# Daughter_Board_2_1.net
KiCad netlist of a schematic drawn in EAGLE
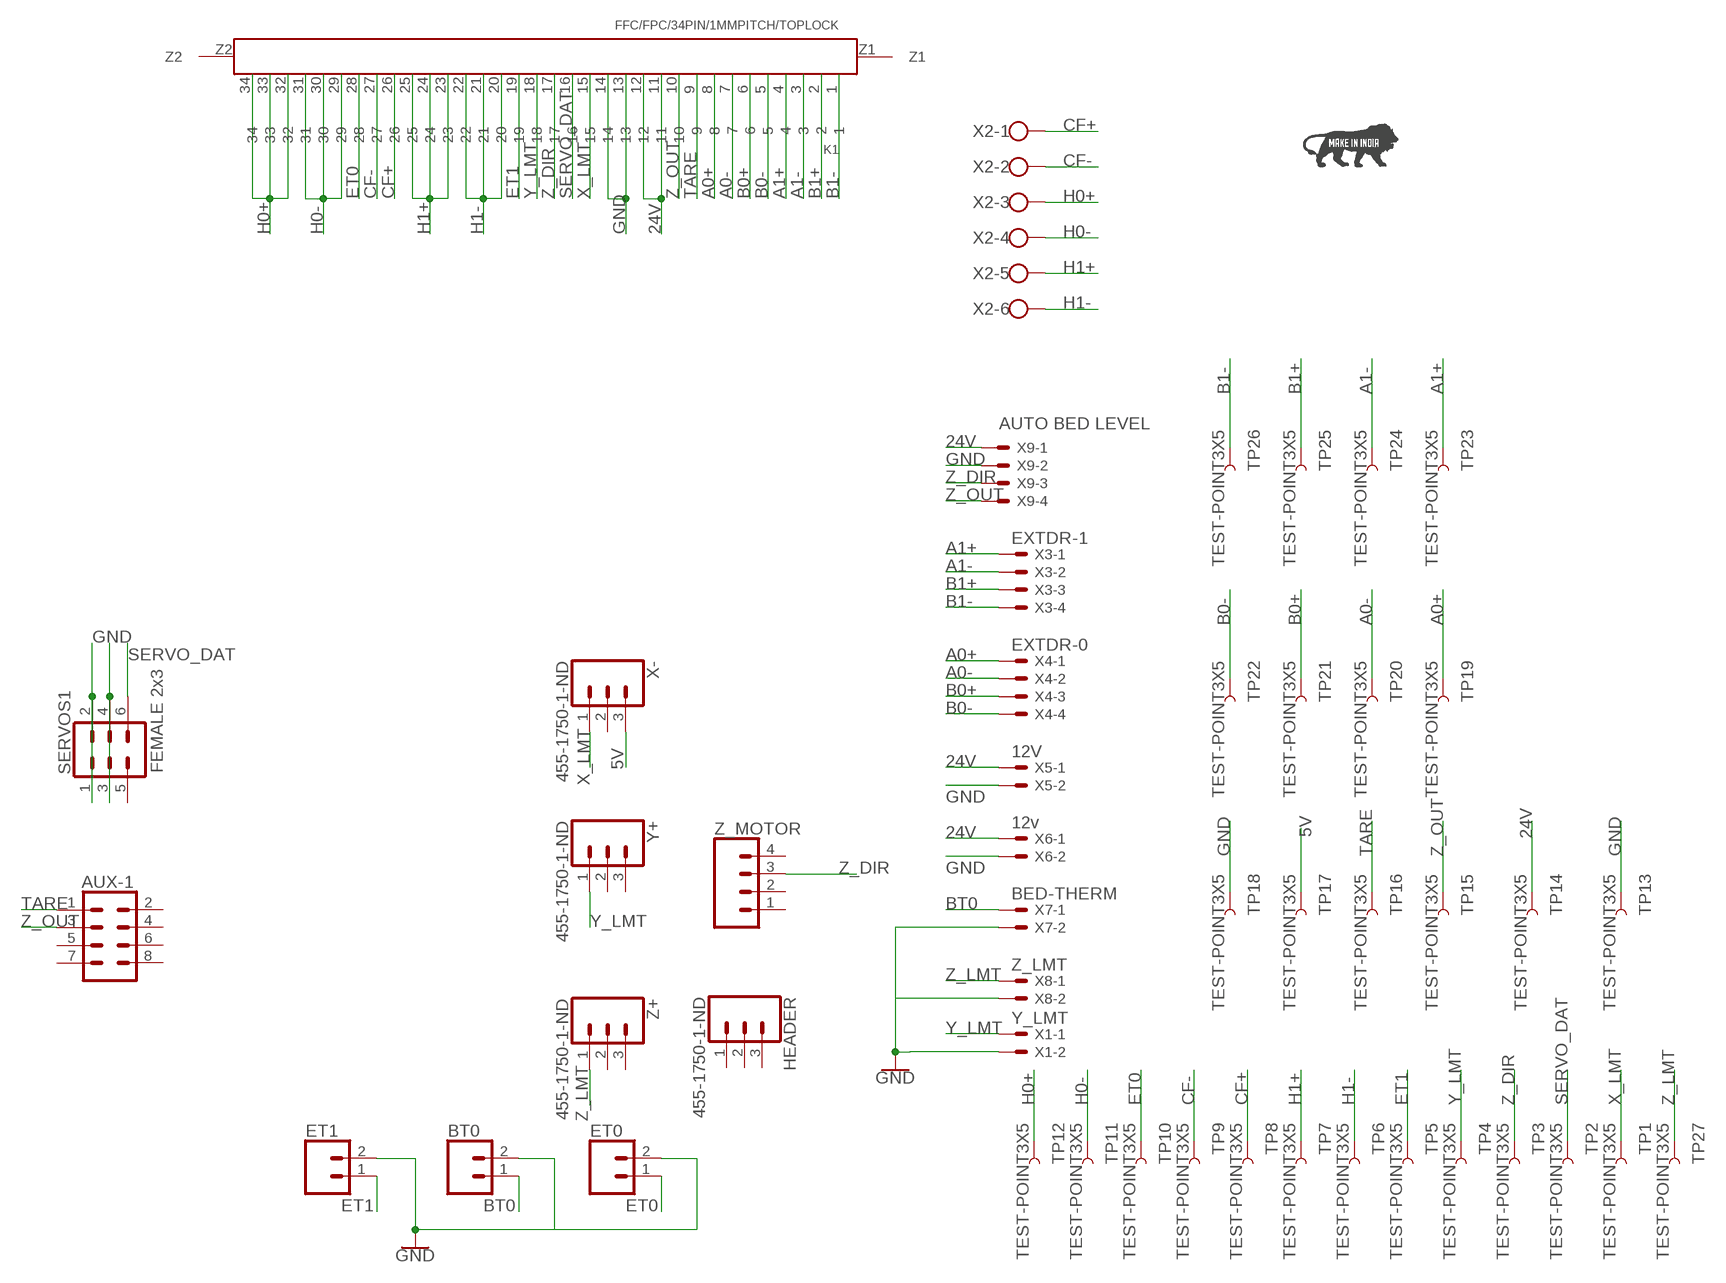
[diagram p0: schematic, sheet 1]

(export (version "E")
  (design (tool "Eeschema 10.0.6"))
  (components
    (comp (ref "AUX-1")
      (value "CONN_04X2")
      (footprint "eagle-import:2X4")
      (libsource (lib "eagle-import") (part "CONN_04X2"))
    )
    (comp (ref "BT0")
      (value "CONN_02")
      (footprint "eagle-import:1X02")
      (libsource (lib "eagle-import") (part "CONN_02"))
    )
    (comp (ref "ET0")
      (value "CONN_02")
      (footprint "eagle-import:1X02")
      (libsource (lib "eagle-import") (part "CONN_02"))
    )
    (comp (ref "ET1")
      (value "CONN_02")
      (footprint "eagle-import:1X02")
      (libsource (lib "eagle-import") (part "CONN_02"))
    )
    (comp (ref "HEADER")
      (value "455-1750-1-ND")
      (footprint "eagle-import:1X03")
      (libsource (lib "eagle-import") (part "CONN_03"))
    )
    (comp (ref "K1")
      (value "FFC/FPC/34PIN/1MMPITCH/TOPLOCK")
      (footprint "eagle-import:34PIN_1MMPITCH_FFC_FPC")
      (libsource (lib "eagle-import") (part "FFC/FPC/34PIN/1MMPITCH/TOPLOCK"))
    )
    (comp (ref "SERVOS1")
      (value "FEMALE 2x3")
      (footprint "eagle-import:2X3")
      (libsource (lib "eagle-import") (part "CONN_03X2FEMALE"))
    )
    (comp (ref "TP1")
      (value "TEST-POINT3X5")
      (footprint "eagle-import:PAD.03X.05")
      (libsource (lib "eagle-import") (part "TEST-POINT3X5"))
    )
    (comp (ref "TP2")
      (value "TEST-POINT3X5")
      (footprint "eagle-import:PAD.03X.05")
      (libsource (lib "eagle-import") (part "TEST-POINT3X5"))
    )
    (comp (ref "TP3")
      (value "TEST-POINT3X5")
      (footprint "eagle-import:PAD.03X.05")
      (libsource (lib "eagle-import") (part "TEST-POINT3X5"))
    )
    (comp (ref "TP4")
      (value "TEST-POINT3X5")
      (footprint "eagle-import:PAD.03X.05")
      (libsource (lib "eagle-import") (part "TEST-POINT3X5"))
    )
    (comp (ref "TP5")
      (value "TEST-POINT3X5")
      (footprint "eagle-import:PAD.03X.05")
      (libsource (lib "eagle-import") (part "TEST-POINT3X5"))
    )
    (comp (ref "TP6")
      (value "TEST-POINT3X5")
      (footprint "eagle-import:PAD.03X.05")
      (libsource (lib "eagle-import") (part "TEST-POINT3X5"))
    )
    (comp (ref "TP7")
      (value "TEST-POINT3X5")
      (footprint "eagle-import:PAD.03X.05")
      (libsource (lib "eagle-import") (part "TEST-POINT3X5"))
    )
    (comp (ref "TP8")
      (value "TEST-POINT3X5")
      (footprint "eagle-import:PAD.03X.05")
      (libsource (lib "eagle-import") (part "TEST-POINT3X5"))
    )
    (comp (ref "TP9")
      (value "TEST-POINT3X5")
      (footprint "eagle-import:PAD.03X.05")
      (libsource (lib "eagle-import") (part "TEST-POINT3X5"))
    )
    (comp (ref "TP10")
      (value "TEST-POINT3X5")
      (footprint "eagle-import:PAD.03X.05")
      (libsource (lib "eagle-import") (part "TEST-POINT3X5"))
    )
    (comp (ref "TP11")
      (value "TEST-POINT3X5")
      (footprint "eagle-import:PAD.03X.05")
      (libsource (lib "eagle-import") (part "TEST-POINT3X5"))
    )
    (comp (ref "TP12")
      (value "TEST-POINT3X5")
      (footprint "eagle-import:PAD.03X.05")
      (libsource (lib "eagle-import") (part "TEST-POINT3X5"))
    )
    (comp (ref "TP13")
      (value "TEST-POINT3X5")
      (footprint "eagle-import:PAD.03X.05")
      (libsource (lib "eagle-import") (part "TEST-POINT3X5"))
    )
    (comp (ref "TP14")
      (value "TEST-POINT3X5")
      (footprint "eagle-import:PAD.03X.05")
      (libsource (lib "eagle-import") (part "TEST-POINT3X5"))
    )
    (comp (ref "TP15")
      (value "TEST-POINT3X5")
      (footprint "eagle-import:PAD.03X.05")
      (libsource (lib "eagle-import") (part "TEST-POINT3X5"))
    )
    (comp (ref "TP16")
      (value "TEST-POINT3X5")
      (footprint "eagle-import:PAD.03X.05")
      (libsource (lib "eagle-import") (part "TEST-POINT3X5"))
    )
    (comp (ref "TP17")
      (value "TEST-POINT3X5")
      (footprint "eagle-import:PAD.03X.05")
      (libsource (lib "eagle-import") (part "TEST-POINT3X5"))
    )
    (comp (ref "TP18")
      (value "TEST-POINT3X5")
      (footprint "eagle-import:PAD.03X.05")
      (libsource (lib "eagle-import") (part "TEST-POINT3X5"))
    )
    (comp (ref "TP19")
      (value "TEST-POINT3X5")
      (footprint "eagle-import:PAD.03X.05")
      (libsource (lib "eagle-import") (part "TEST-POINT3X5"))
    )
    (comp (ref "TP20")
      (value "TEST-POINT3X5")
      (footprint "eagle-import:PAD.03X.05")
      (libsource (lib "eagle-import") (part "TEST-POINT3X5"))
    )
    (comp (ref "TP21")
      (value "TEST-POINT3X5")
      (footprint "eagle-import:PAD.03X.05")
      (libsource (lib "eagle-import") (part "TEST-POINT3X5"))
    )
    (comp (ref "TP22")
      (value "TEST-POINT3X5")
      (footprint "eagle-import:PAD.03X.05")
      (libsource (lib "eagle-import") (part "TEST-POINT3X5"))
    )
    (comp (ref "TP23")
      (value "TEST-POINT3X5")
      (footprint "eagle-import:PAD.03X.05")
      (libsource (lib "eagle-import") (part "TEST-POINT3X5"))
    )
    (comp (ref "TP24")
      (value "TEST-POINT3X5")
      (footprint "eagle-import:PAD.03X.05")
      (libsource (lib "eagle-import") (part "TEST-POINT3X5"))
    )
    (comp (ref "TP25")
      (value "TEST-POINT3X5")
      (footprint "eagle-import:PAD.03X.05")
      (libsource (lib "eagle-import") (part "TEST-POINT3X5"))
    )
    (comp (ref "TP26")
      (value "TEST-POINT3X5")
      (footprint "eagle-import:PAD.03X.05")
      (libsource (lib "eagle-import") (part "TEST-POINT3X5"))
    )
    (comp (ref "TP27")
      (value "TEST-POINT3X5")
      (footprint "eagle-import:PAD.03X.05")
      (libsource (lib "eagle-import") (part "TEST-POINT3X5"))
    )
    (comp (ref "U$2")
      (value "MAKEININDIA")
      (footprint "eagle-import:MAKEININDIA")
      (libsource (lib "eagle-import") (part "MAKEININDIA"))
    )
    (comp (ref "X-")
      (value "455-1750-1-ND")
      (footprint "eagle-import:1X03")
      (libsource (lib "eagle-import") (part "CONN_03"))
    )
    (comp (ref "X1")
      (value "Y_LMT")
      (footprint "eagle-import:JST-XH-02-PACKAGE-LONG-PAD")
      (libsource (lib "eagle-import") (part "JST-XH-02-PIN-LONG-PAD"))
    )
    (comp (ref "X2")
      (value "W237-6")
      (footprint "eagle-import:W237-6")
      (libsource (lib "eagle-import") (part "W237-6"))
    )
    (comp (ref "X3")
      (value "EXTDR-1")
      (footprint "eagle-import:JST-XH-04-PACKAGE-LONG-PAD")
      (libsource (lib "eagle-import") (part "JST-XH-04-PIN-LONG-PAD"))
    )
    (comp (ref "X4")
      (value "EXTDR-0")
      (footprint "eagle-import:JST-XH-04-PACKAGE-LONG-PAD")
      (libsource (lib "eagle-import") (part "JST-XH-04-PIN-LONG-PAD"))
    )
    (comp (ref "X5")
      (value "12V")
      (footprint "eagle-import:JST-XH-02-PACKAGE-LONG-PAD")
      (libsource (lib "eagle-import") (part "JST-XH-02-PIN-LONG-PAD"))
    )
    (comp (ref "X6")
      (value "12v")
      (footprint "eagle-import:JST-XH-02-PACKAGE-LONG-PAD")
      (libsource (lib "eagle-import") (part "JST-XH-02-PIN-LONG-PAD"))
    )
    (comp (ref "X7")
      (value "BED-THERM")
      (footprint "eagle-import:JST-XH-02-PACKAGE-LONG-PAD")
      (libsource (lib "eagle-import") (part "JST-XH-02-PIN-LONG-PAD"))
    )
    (comp (ref "X8")
      (value "Z_LMT")
      (footprint "eagle-import:JST-XH-02-PACKAGE-LONG-PAD")
      (libsource (lib "eagle-import") (part "JST-XH-02-PIN-LONG-PAD"))
    )
    (comp (ref "X9")
      (value "JST-XH-04-PIN-LONG-PAD")
      (footprint "eagle-import:JST-XH-04-PACKAGE-LONG-PAD")
      (fields (field (name "AUTOBEDLEVL") "AUTO BED LEVEL"))
      (libsource (lib "eagle-import") (part "JST-XH-04-PIN-LONG-PAD"))
    )
    (comp (ref "Y+")
      (value "455-1750-1-ND")
      (footprint "eagle-import:1X03")
      (libsource (lib "eagle-import") (part "CONN_03"))
    )
    (comp (ref "Z+")
      (value "455-1750-1-ND")
      (footprint "eagle-import:1X03")
      (libsource (lib "eagle-import") (part "CONN_03"))
    )
    (comp (ref "Z_MOTOR")
      (value "CONN_04")
      (footprint "eagle-import:1X04")
      (libsource (lib "eagle-import") (part "CONN_04"))
    )
  )
  (nets
    (net (code "1") (name "/5V") (class "Default")
      (node (ref "TP17") (pin "P$1") (pinfunction "1_P$1") (pintype "bidirectional"))
      (node (ref "X-") (pin "3") (pinfunction "3_3") (pintype "passive"))
    )
    (net (code "2") (name "/24V") (class "Default")
      (node (ref "K1") (pin "11") (pinfunction "11_11") (pintype "bidirectional"))
      (node (ref "K1") (pin "12") (pinfunction "12_12") (pintype "bidirectional"))
      (node (ref "TP14") (pin "P$1") (pinfunction "1_P$1") (pintype "bidirectional"))
      (node (ref "X5") (pin "1") (pinfunction "S_1") (pintype "passive"))
      (node (ref "X6") (pin "1") (pinfunction "S_1") (pintype "passive"))
      (node (ref "X9") (pin "1") (pinfunction "S_1") (pintype "passive"))
    )
    (net (code "3") (name "/A0+") (class "Default")
      (node (ref "K1") (pin "8") (pinfunction "8_8") (pintype "bidirectional"))
      (node (ref "TP19") (pin "P$1") (pinfunction "1_P$1") (pintype "bidirectional"))
      (node (ref "X4") (pin "1") (pinfunction "S_1") (pintype "passive"))
    )
    (net (code "4") (name "/A0-") (class "Default")
      (node (ref "K1") (pin "7") (pinfunction "7_7") (pintype "bidirectional"))
      (node (ref "TP20") (pin "P$1") (pinfunction "1_P$1") (pintype "bidirectional"))
      (node (ref "X4") (pin "2") (pinfunction "S_2") (pintype "passive"))
    )
    (net (code "5") (name "/A1+") (class "Default")
      (node (ref "K1") (pin "4") (pinfunction "4_4") (pintype "bidirectional"))
      (node (ref "TP23") (pin "P$1") (pinfunction "1_P$1") (pintype "bidirectional"))
      (node (ref "X3") (pin "1") (pinfunction "S_1") (pintype "passive"))
    )
    (net (code "6") (name "/A1-") (class "Default")
      (node (ref "K1") (pin "3") (pinfunction "3_3") (pintype "bidirectional"))
      (node (ref "TP24") (pin "P$1") (pinfunction "1_P$1") (pintype "bidirectional"))
      (node (ref "X3") (pin "2") (pinfunction "S_2") (pintype "passive"))
    )
    (net (code "7") (name "/B0+") (class "Default")
      (node (ref "K1") (pin "6") (pinfunction "6_6") (pintype "bidirectional"))
      (node (ref "TP21") (pin "P$1") (pinfunction "1_P$1") (pintype "bidirectional"))
      (node (ref "X4") (pin "3") (pinfunction "S_3") (pintype "passive"))
    )
    (net (code "8") (name "/B0-") (class "Default")
      (node (ref "K1") (pin "5") (pinfunction "5_5") (pintype "bidirectional"))
      (node (ref "TP22") (pin "P$1") (pinfunction "1_P$1") (pintype "bidirectional"))
      (node (ref "X4") (pin "4") (pinfunction "S_4") (pintype "passive"))
    )
    (net (code "9") (name "/B1+") (class "Default")
      (node (ref "K1") (pin "2") (pinfunction "2_2") (pintype "bidirectional"))
      (node (ref "TP25") (pin "P$1") (pinfunction "1_P$1") (pintype "bidirectional"))
      (node (ref "X3") (pin "3") (pinfunction "S_3") (pintype "passive"))
    )
    (net (code "10") (name "/B1-") (class "Default")
      (node (ref "K1") (pin "1") (pinfunction "1_1") (pintype "bidirectional"))
      (node (ref "TP26") (pin "P$1") (pinfunction "1_P$1") (pintype "bidirectional"))
      (node (ref "X3") (pin "4") (pinfunction "S_4") (pintype "passive"))
    )
    (net (code "11") (name "/BT0") (class "Default")
      (node (ref "BT0") (pin "1") (pinfunction "1_1") (pintype "passive"))
      (node (ref "X7") (pin "1") (pinfunction "S_1") (pintype "passive"))
    )
    (net (code "12") (name "/CF+") (class "Default")
      (node (ref "K1") (pin "26") (pinfunction "26_26") (pintype "bidirectional"))
      (node (ref "TP8") (pin "P$1") (pinfunction "1_P$1") (pintype "bidirectional"))
      (node (ref "X2") (pin "1") (pinfunction "KL_1") (pintype "passive"))
    )
    (net (code "13") (name "/CF-") (class "Default")
      (node (ref "K1") (pin "27") (pinfunction "27_27") (pintype "bidirectional"))
      (node (ref "TP9") (pin "P$1") (pinfunction "1_P$1") (pintype "bidirectional"))
      (node (ref "X2") (pin "2") (pinfunction "KL_2") (pintype "passive"))
    )
    (net (code "14") (name "/ET0") (class "Default")
      (node (ref "ET0") (pin "1") (pinfunction "1_1") (pintype "passive"))
      (node (ref "K1") (pin "28") (pinfunction "28_28") (pintype "bidirectional"))
      (node (ref "TP10") (pin "P$1") (pinfunction "1_P$1") (pintype "bidirectional"))
    )
    (net (code "15") (name "/ET1") (class "Default")
      (node (ref "ET1") (pin "1") (pinfunction "1_1") (pintype "passive"))
      (node (ref "K1") (pin "19") (pinfunction "19_19") (pintype "bidirectional"))
      (node (ref "TP5") (pin "P$1") (pinfunction "1_P$1") (pintype "bidirectional"))
    )
    (net (code "16") (name "/H0+") (class "Default")
      (node (ref "K1") (pin "32") (pinfunction "32_32") (pintype "bidirectional"))
      (node (ref "K1") (pin "33") (pinfunction "33_33") (pintype "bidirectional"))
      (node (ref "K1") (pin "34") (pinfunction "34_34") (pintype "bidirectional"))
      (node (ref "TP12") (pin "P$1") (pinfunction "1_P$1") (pintype "bidirectional"))
      (node (ref "X2") (pin "3") (pinfunction "KL_3") (pintype "passive"))
    )
    (net (code "17") (name "/H0-") (class "Default")
      (node (ref "K1") (pin "29") (pinfunction "29_29") (pintype "bidirectional"))
      (node (ref "K1") (pin "30") (pinfunction "30_30") (pintype "bidirectional"))
      (node (ref "K1") (pin "31") (pinfunction "31_31") (pintype "bidirectional"))
      (node (ref "TP11") (pin "P$1") (pinfunction "1_P$1") (pintype "bidirectional"))
      (node (ref "X2") (pin "4") (pinfunction "KL_4") (pintype "passive"))
    )
    (net (code "18") (name "/H1+") (class "Default")
      (node (ref "K1") (pin "23") (pinfunction "23_23") (pintype "bidirectional"))
      (node (ref "K1") (pin "24") (pinfunction "24_24") (pintype "bidirectional"))
      (node (ref "K1") (pin "25") (pinfunction "25_25") (pintype "bidirectional"))
      (node (ref "TP7") (pin "P$1") (pinfunction "1_P$1") (pintype "bidirectional"))
      (node (ref "X2") (pin "5") (pinfunction "KL_5") (pintype "passive"))
    )
    (net (code "19") (name "/H1-") (class "Default")
      (node (ref "K1") (pin "20") (pinfunction "20_20") (pintype "bidirectional"))
      (node (ref "K1") (pin "21") (pinfunction "21_21") (pintype "bidirectional"))
      (node (ref "K1") (pin "22") (pinfunction "22_22") (pintype "bidirectional"))
      (node (ref "TP6") (pin "P$1") (pinfunction "1_P$1") (pintype "bidirectional"))
      (node (ref "X2") (pin "6") (pinfunction "KL_6") (pintype "passive"))
    )
    (net (code "20") (name "/SERVO_DAT") (class "Default")
      (node (ref "K1") (pin "16") (pinfunction "16_16") (pintype "bidirectional"))
      (node (ref "SERVOS1") (pin "6") (pinfunction "6_6") (pintype "bidirectional"))
      (node (ref "TP2") (pin "P$1") (pinfunction "1_P$1") (pintype "bidirectional"))
    )
    (net (code "21") (name "/TARE") (class "Default")
      (node (ref "AUX-1") (pin "1") (pinfunction "1_1") (pintype "passive"))
      (node (ref "K1") (pin "9") (pinfunction "9_9") (pintype "bidirectional"))
      (node (ref "TP16") (pin "P$1") (pinfunction "1_P$1") (pintype "bidirectional"))
    )
    (net (code "22") (name "/X_LMT") (class "Default")
      (node (ref "K1") (pin "15") (pinfunction "15_15") (pintype "bidirectional"))
      (node (ref "TP1") (pin "P$1") (pinfunction "1_P$1") (pintype "bidirectional"))
      (node (ref "X-") (pin "1") (pinfunction "1_1") (pintype "passive"))
    )
    (net (code "23") (name "/Y_LMT") (class "Default")
      (node (ref "K1") (pin "18") (pinfunction "18_18") (pintype "bidirectional"))
      (node (ref "TP4") (pin "P$1") (pinfunction "1_P$1") (pintype "bidirectional"))
      (node (ref "X1") (pin "1") (pinfunction "S_1") (pintype "passive"))
      (node (ref "Y+") (pin "1") (pinfunction "1_1") (pintype "passive"))
    )
    (net (code "24") (name "/Z_DIR") (class "Default")
      (node (ref "K1") (pin "17") (pinfunction "17_17") (pintype "bidirectional"))
      (node (ref "TP3") (pin "P$1") (pinfunction "1_P$1") (pintype "bidirectional"))
      (node (ref "X9") (pin "3") (pinfunction "S_3") (pintype "passive"))
      (node (ref "Z_MOTOR") (pin "3") (pinfunction "3_3") (pintype "passive"))
    )
    (net (code "25") (name "/Z_LMT") (class "Default")
      (node (ref "TP27") (pin "P$1") (pinfunction "1_P$1") (pintype "bidirectional"))
      (node (ref "X8") (pin "1") (pinfunction "S_1") (pintype "passive"))
      (node (ref "Z+") (pin "1") (pinfunction "1_1") (pintype "passive"))
    )
    (net (code "26") (name "/Z_OUT") (class "Default")
      (node (ref "AUX-1") (pin "3") (pinfunction "3_3") (pintype "passive"))
      (node (ref "K1") (pin "10") (pinfunction "10_10") (pintype "bidirectional"))
      (node (ref "TP15") (pin "P$1") (pinfunction "1_P$1") (pintype "bidirectional"))
      (node (ref "X9") (pin "4") (pinfunction "S_4") (pintype "passive"))
    )
    (net (code "27") (name "GND") (class "Default")
      (node (ref "BT0") (pin "2") (pinfunction "2_2") (pintype "passive"))
      (node (ref "ET0") (pin "2") (pinfunction "2_2") (pintype "passive"))
      (node (ref "ET1") (pin "2") (pinfunction "2_2") (pintype "passive"))
      (node (ref "K1") (pin "13") (pinfunction "13_13") (pintype "bidirectional"))
      (node (ref "K1") (pin "14") (pinfunction "14_14") (pintype "bidirectional"))
      (node (ref "SERVOS1") (pin "1") (pinfunction "1_1") (pintype "bidirectional"))
      (node (ref "SERVOS1") (pin "2") (pinfunction "2_2") (pintype "bidirectional"))
      (node (ref "TP13") (pin "P$1") (pinfunction "1_P$1") (pintype "bidirectional"))
      (node (ref "TP18") (pin "P$1") (pinfunction "1_P$1") (pintype "bidirectional"))
      (node (ref "X1") (pin "2") (pinfunction "S_2") (pintype "passive"))
      (node (ref "X5") (pin "2") (pinfunction "S_2") (pintype "passive"))
      (node (ref "X6") (pin "2") (pinfunction "S_2") (pintype "passive"))
      (node (ref "X7") (pin "2") (pinfunction "S_2") (pintype "passive"))
      (node (ref "X8") (pin "2") (pinfunction "S_2") (pintype "passive"))
      (node (ref "X9") (pin "2") (pinfunction "S_2") (pintype "passive"))
    )
    (net (code "28") (name "Net-(SERVOS1-Pad3)") (class "Default")
      (node (ref "SERVOS1") (pin "3") (pinfunction "3_3") (pintype "bidirectional"))
      (node (ref "SERVOS1") (pin "4") (pinfunction "4_4") (pintype "bidirectional"))
    )
    (net (code "29") (name "unconnected-(AUX-1-Pad2)") (class "Default")
      (node (ref "AUX-1") (pin "2") (pinfunction "2_2") (pintype "passive"))
    )
    (net (code "30") (name "unconnected-(AUX-1-Pad4)") (class "Default")
      (node (ref "AUX-1") (pin "4") (pinfunction "4_4") (pintype "passive"))
    )
    (net (code "31") (name "unconnected-(AUX-1-Pad5)") (class "Default")
      (node (ref "AUX-1") (pin "5") (pinfunction "5_5") (pintype "passive"))
    )
    (net (code "32") (name "unconnected-(AUX-1-Pad6)") (class "Default")
      (node (ref "AUX-1") (pin "6") (pinfunction "6_6") (pintype "passive"))
    )
    (net (code "33") (name "unconnected-(AUX-1-Pad7)") (class "Default")
      (node (ref "AUX-1") (pin "7") (pinfunction "7_7") (pintype "passive"))
    )
    (net (code "34") (name "unconnected-(AUX-1-Pad8)") (class "Default")
      (node (ref "AUX-1") (pin "8") (pinfunction "8_8") (pintype "passive"))
    )
    (net (code "35") (name "unconnected-(HEADER-Pad1)") (class "Default")
      (node (ref "HEADER") (pin "1") (pinfunction "1_1") (pintype "passive"))
    )
    (net (code "36") (name "unconnected-(HEADER-Pad2)") (class "Default")
      (node (ref "HEADER") (pin "2") (pinfunction "2_2") (pintype "passive"))
    )
    (net (code "37") (name "unconnected-(HEADER-Pad3)") (class "Default")
      (node (ref "HEADER") (pin "3") (pinfunction "3_3") (pintype "passive"))
    )
    (net (code "38") (name "unconnected-(K1-PadZ1)") (class "Default")
      (node (ref "K1") (pin "Z1") (pinfunction "Z1_Z1") (pintype "bidirectional"))
    )
    (net (code "39") (name "unconnected-(K1-PadZ2)") (class "Default")
      (node (ref "K1") (pin "Z2") (pinfunction "Z2_Z2") (pintype "bidirectional"))
    )
    (net (code "40") (name "unconnected-(SERVOS1-Pad5)") (class "Default")
      (node (ref "SERVOS1") (pin "5") (pinfunction "5_5") (pintype "bidirectional"))
    )
    (net (code "41") (name "unconnected-(X--Pad2)") (class "Default")
      (node (ref "X-") (pin "2") (pinfunction "2_2") (pintype "passive"))
    )
    (net (code "42") (name "unconnected-(Y+-Pad2)") (class "Default")
      (node (ref "Y+") (pin "2") (pinfunction "2_2") (pintype "passive"))
    )
    (net (code "43") (name "unconnected-(Y+-Pad3)") (class "Default")
      (node (ref "Y+") (pin "3") (pinfunction "3_3") (pintype "passive"))
    )
    (net (code "44") (name "unconnected-(Z+-Pad2)") (class "Default")
      (node (ref "Z+") (pin "2") (pinfunction "2_2") (pintype "passive"))
    )
    (net (code "45") (name "unconnected-(Z+-Pad3)") (class "Default")
      (node (ref "Z+") (pin "3") (pinfunction "3_3") (pintype "passive"))
    )
    (net (code "46") (name "unconnected-(Z_MOTOR-Pad1)") (class "Default")
      (node (ref "Z_MOTOR") (pin "1") (pinfunction "1_1") (pintype "passive"))
    )
    (net (code "47") (name "unconnected-(Z_MOTOR-Pad2)") (class "Default")
      (node (ref "Z_MOTOR") (pin "2") (pinfunction "2_2") (pintype "passive"))
    )
    (net (code "48") (name "unconnected-(Z_MOTOR-Pad4)") (class "Default")
      (node (ref "Z_MOTOR") (pin "4") (pinfunction "4_4") (pintype "passive"))
    )
  )
)
